# ETHERNET.net
KiCad netlist of a schematic drawn in Altium Designer
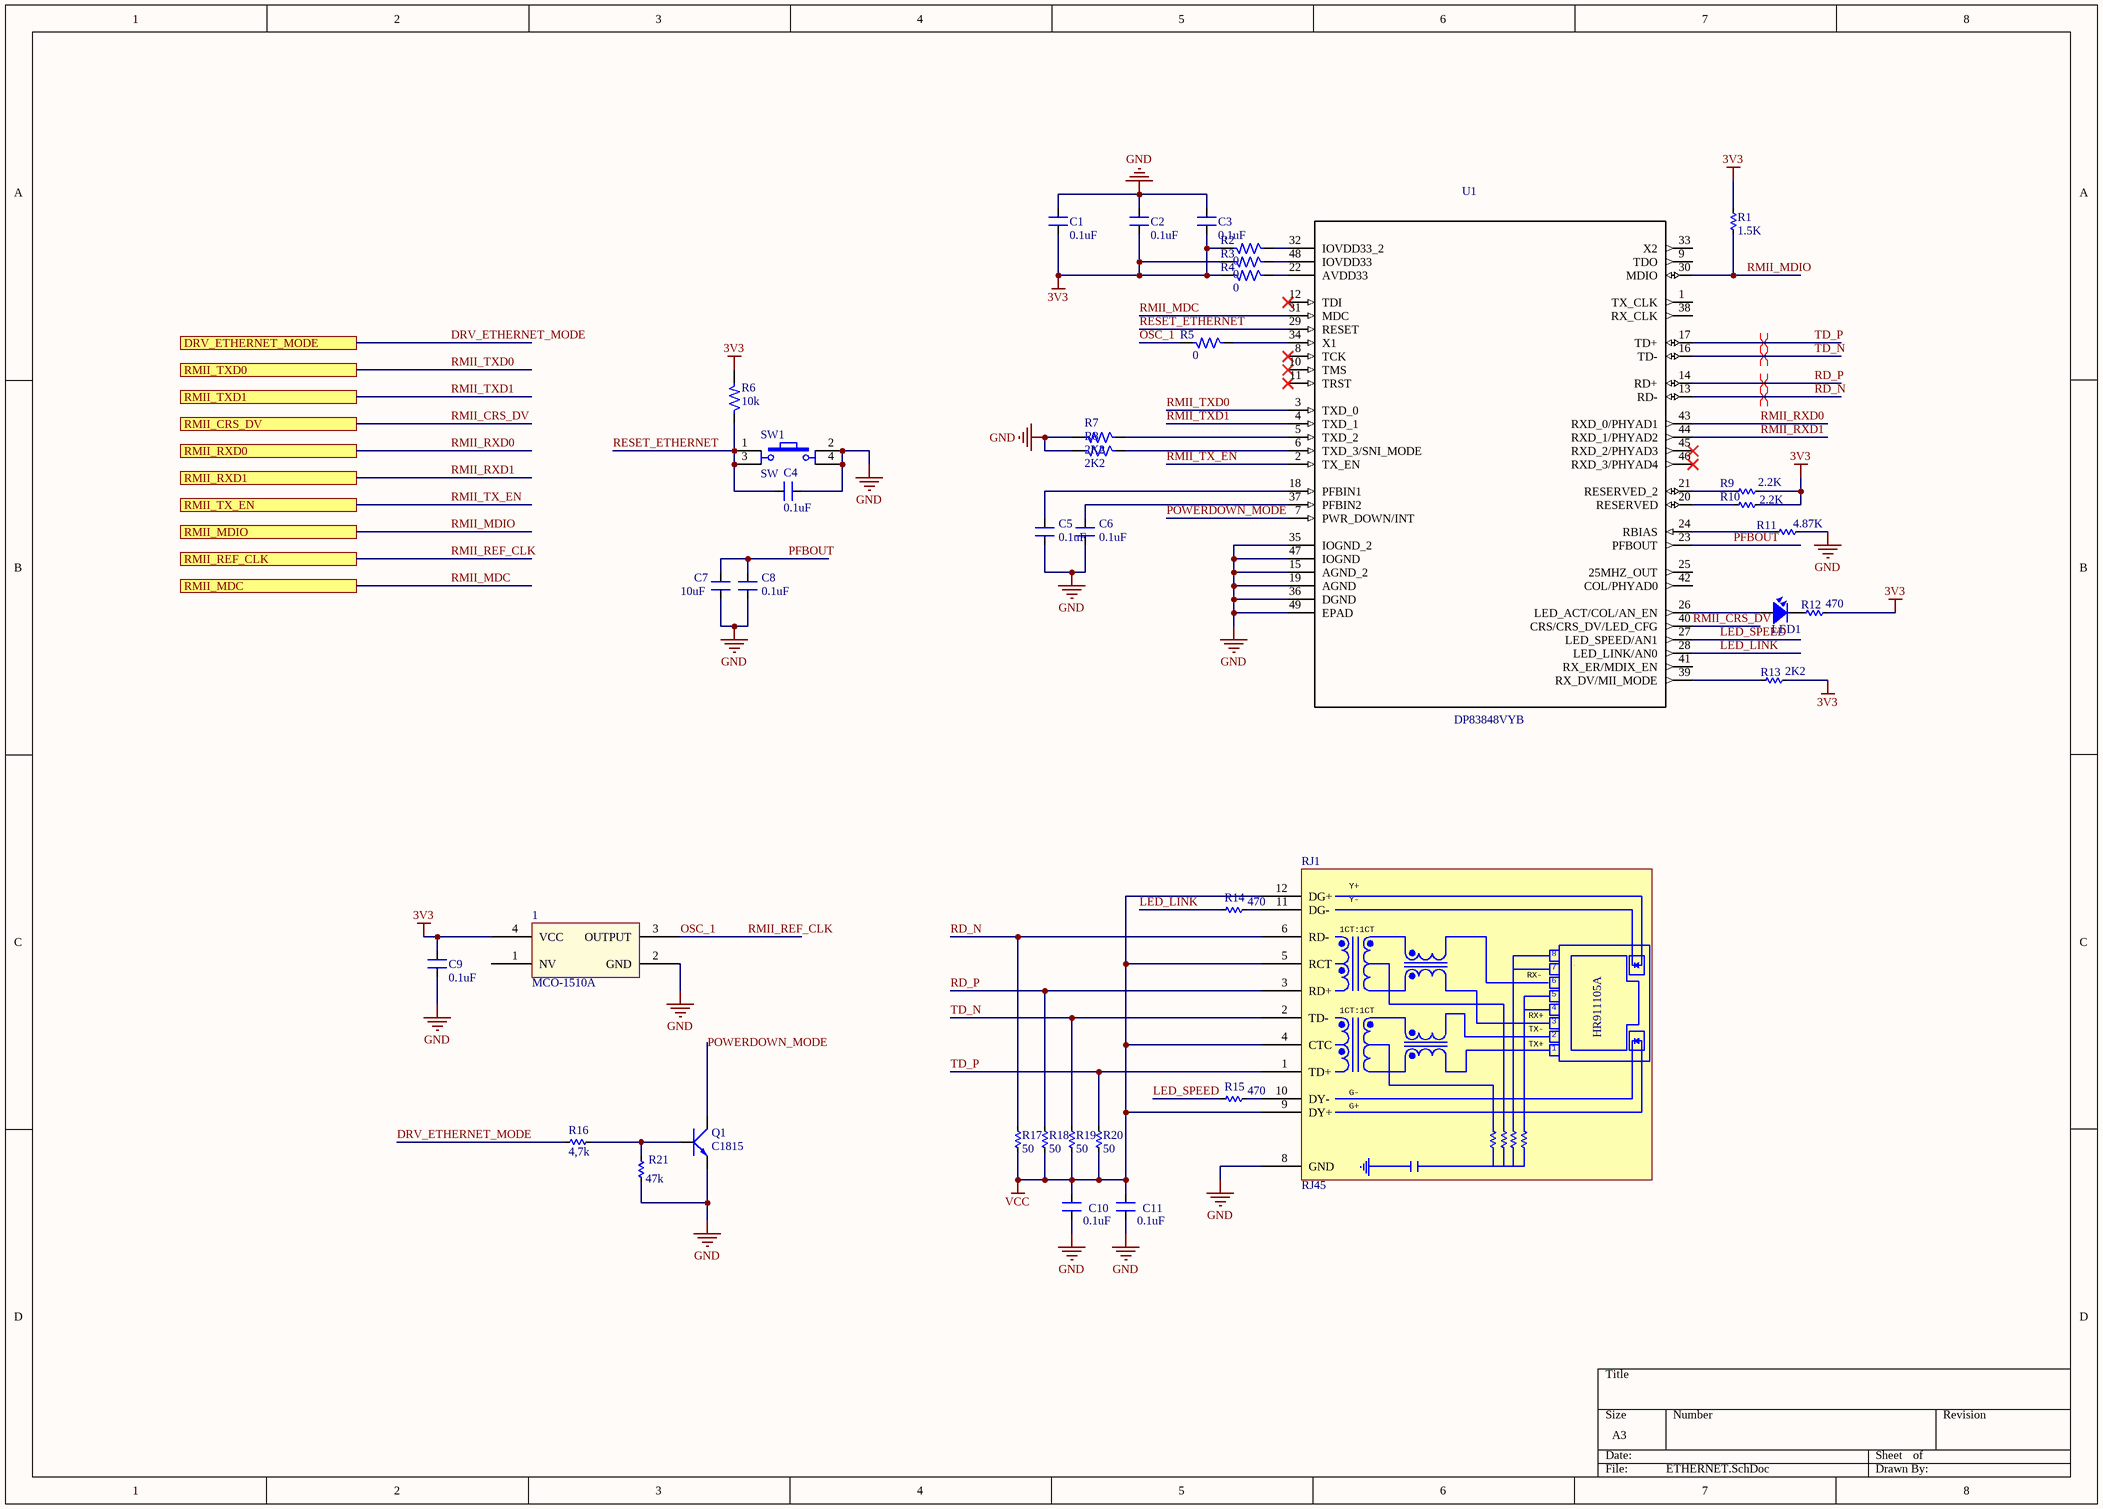
[diagram p0: ETHERNET.SchDoc]

(export (version "E")
  (design (tool "Eeschema 10.0.6"))
  (components
    (comp (ref "1") (value "MCO-1510A") (footprint "OSC_1510B") (libsource (lib "my_lib") (part "OSC50MhZ")))
    (comp (ref "C1")
      (value "0.1uF")
      (footprint "res 0805 - duplicate")
      (description "Cap SMD")
      (libsource (lib "PART") (part "CM"))
    )
    (comp (ref "C2")
      (value "0.1uF")
      (footprint "res 0805 - duplicate")
      (description "Cap SMD")
      (libsource (lib "PART") (part "CM"))
    )
    (comp (ref "C3")
      (value "0.1uF")
      (footprint "res 0805 - duplicate")
      (description "Cap SMD")
      (libsource (lib "PART") (part "CM"))
    )
    (comp (ref "C4")
      (value "0.1uF")
      (footprint "res 0805 - duplicate")
      (description "Cap SMD")
      (libsource (lib "PART") (part "CM"))
    )
    (comp (ref "C5")
      (value "0.1uF")
      (footprint "res 0805 - duplicate")
      (description "Cap SMD")
      (libsource (lib "PART") (part "CM"))
    )
    (comp (ref "C6")
      (value "0.1uF")
      (footprint "res 0805 - duplicate")
      (description "Cap SMD")
      (libsource (lib "PART") (part "CM"))
    )
    (comp (ref "C7")
      (value "10uF")
      (footprint "res 0805 - duplicate")
      (description "Cap SMD")
      (libsource (lib "PART") (part "CM"))
    )
    (comp (ref "C8")
      (value "0.1uF")
      (footprint "res 0805 - duplicate")
      (description "Cap SMD")
      (libsource (lib "PART") (part "CM"))
    )
    (comp (ref "C9")
      (value "0.1uF")
      (footprint "res 0805 - duplicate")
      (description "Cap SMD")
      (libsource (lib "PART") (part "CM"))
    )
    (comp (ref "C10")
      (value "0.1uF")
      (footprint "res 0805 - duplicate")
      (description "Cap SMD")
      (libsource (lib "PART") (part "CM"))
    )
    (comp (ref "C11")
      (value "0.1uF")
      (footprint "res 0805 - duplicate")
      (description "Cap SMD")
      (libsource (lib "PART") (part "CM"))
    )
    (comp (ref "LED1")
      (value "LED")
      (footprint "res 0805 - duplicate")
      (libsource (lib "LIBRARYabc") (part "LED SMD"))
    )
    (comp (ref "Q1")
      (value "C1815")
      (footprint "SOT23B")
      (description "NPN 600mW, ECB")
      (libsource (lib "syhaunguyen") (part "C1815"))
    )
    (comp (ref "R1")
      (value "1.5K")
      (footprint "res 0805 - duplicate")
      (description "Resistor")
      (fields
        (field (name "MANUFACTURER") "Generic Components")
        (field (name "PUBLISHER") "Altium Hobart Technology Centre")
      )
      (libsource (lib "LIBRARYabc") (part "Res-SMD"))
    )
    (comp (ref "R2")
      (value "0")
      (footprint "res 0805 - duplicate")
      (description "Resistor 1/4W")
      (libsource (lib "syhaunguyen") (part "R"))
    )
    (comp (ref "R3")
      (value "0")
      (footprint "res 0805 - duplicate")
      (description "Resistor 1/4W")
      (libsource (lib "syhaunguyen") (part "R"))
    )
    (comp (ref "R4")
      (value "0")
      (footprint "res 0805 - duplicate")
      (description "Resistor 1/4W")
      (libsource (lib "syhaunguyen") (part "R"))
    )
    (comp (ref "R5")
      (value "0")
      (footprint "res 0805 - duplicate")
      (description "Resistor 1/4W")
      (libsource (lib "syhaunguyen") (part "R"))
    )
    (comp (ref "R6")
      (value "10k")
      (footprint "res 0805 - duplicate")
      (description "Resistor 1/4W")
      (libsource (lib "syhaunguyen") (part "R"))
    )
    (comp (ref "R7")
      (value "2K2")
      (footprint "res 0805 - duplicate")
      (description "Resistor 1/4W")
      (libsource (lib "syhaunguyen") (part "R"))
    )
    (comp (ref "R8")
      (value "2K2")
      (footprint "res 0805 - duplicate")
      (description "Resistor 1/4W")
      (libsource (lib "syhaunguyen") (part "R"))
    )
    (comp (ref "R9")
      (value "2.2K")
      (footprint "res 0805 - duplicate")
      (description "Resistor")
      (fields
        (field (name "MANUFACTURER") "Generic Components")
        (field (name "PUBLISHER") "Altium Hobart Technology Centre")
      )
      (libsource (lib "LIBRARYabc") (part "Res-SMD"))
    )
    (comp (ref "R10")
      (value "2.2K")
      (footprint "res 0805 - duplicate")
      (description "Resistor")
      (fields
        (field (name "MANUFACTURER") "Generic Components")
        (field (name "PUBLISHER") "Altium Hobart Technology Centre")
      )
      (libsource (lib "LIBRARYabc") (part "Res-SMD"))
    )
    (comp (ref "R11")
      (value "4.87K")
      (footprint "res 0805 - duplicate")
      (description "Resistor")
      (fields
        (field (name "MANUFACTURER") "Generic Components")
        (field (name "PUBLISHER") "Altium Hobart Technology Centre")
      )
      (libsource (lib "LIBRARYabc") (part "Res-SMD"))
    )
    (comp (ref "R12")
      (value "470")
      (footprint "res 0805 - duplicate")
      (description "Resistor")
      (fields
        (field (name "MANUFACTURER") "Generic Components")
        (field (name "PUBLISHER") "Altium Hobart Technology Centre")
      )
      (libsource (lib "LIBRARYabc") (part "Res-SMD"))
    )
    (comp (ref "R13")
      (value "2K2")
      (footprint "res 0805 - duplicate")
      (description "Resistor")
      (fields
        (field (name "MANUFACTURER") "Generic Components")
        (field (name "PUBLISHER") "Altium Hobart Technology Centre")
      )
      (libsource (lib "LIBRARYabc") (part "Res-SMD"))
    )
    (comp (ref "R14")
      (value "470")
      (footprint "res 0805 - duplicate")
      (description "Resistor")
      (fields
        (field (name "MANUFACTURER") "Generic Components")
        (field (name "PUBLISHER") "Altium Hobart Technology Centre")
      )
      (libsource (lib "LIBRARYabc") (part "Res-SMD"))
    )
    (comp (ref "R15")
      (value "470")
      (footprint "res 0805 - duplicate")
      (description "Resistor")
      (fields
        (field (name "MANUFACTURER") "Generic Components")
        (field (name "PUBLISHER") "Altium Hobart Technology Centre")
      )
      (libsource (lib "LIBRARYabc") (part "Res-SMD"))
    )
    (comp (ref "R16")
      (value "4,7k")
      (footprint "res 0805 - duplicate")
      (description "Resistor")
      (fields
        (field (name "MANUFACTURER") "Generic Components")
        (field (name "PUBLISHER") "Altium Hobart Technology Centre")
      )
      (libsource (lib "LIBRARYabc") (part "Res-SMD"))
    )
    (comp (ref "R17")
      (value "50")
      (footprint "res 0805 - duplicate")
      (description "Resistor")
      (fields
        (field (name "MANUFACTURER") "Generic Components")
        (field (name "PUBLISHER") "Altium Hobart Technology Centre")
      )
      (libsource (lib "LIBRARYabc") (part "Res-SMD"))
    )
    (comp (ref "R18")
      (value "50")
      (footprint "res 0805 - duplicate")
      (description "Resistor")
      (fields
        (field (name "MANUFACTURER") "Generic Components")
        (field (name "PUBLISHER") "Altium Hobart Technology Centre")
      )
      (libsource (lib "LIBRARYabc") (part "Res-SMD"))
    )
    (comp (ref "R19")
      (value "50")
      (footprint "res 0805 - duplicate")
      (description "Resistor")
      (fields
        (field (name "MANUFACTURER") "Generic Components")
        (field (name "PUBLISHER") "Altium Hobart Technology Centre")
      )
      (libsource (lib "LIBRARYabc") (part "Res-SMD"))
    )
    (comp (ref "R20")
      (value "50")
      (footprint "res 0805 - duplicate")
      (description "Resistor")
      (fields
        (field (name "MANUFACTURER") "Generic Components")
        (field (name "PUBLISHER") "Altium Hobart Technology Centre")
      )
      (libsource (lib "LIBRARYabc") (part "Res-SMD"))
    )
    (comp (ref "R21")
      (value "47k")
      (footprint "res 0805 - duplicate")
      (description "Resistor")
      (fields
        (field (name "MANUFACTURER") "Generic Components")
        (field (name "PUBLISHER") "Altium Hobart Technology Centre")
      )
      (libsource (lib "LIBRARYabc") (part "Res-SMD"))
    )
    (comp (ref "RJ1")
      (value "RJ45")
      (footprint "RJ45 Tranfomer")
      (libsource (lib "syhaunguyen") (part "RJ45 - Tranfomer"))
    )
    (comp (ref "SW1")
      (value "SW")
      (footprint "button")
      (description "Switch button 4 pin")
      (libsource (lib "syhaunguyen") (part "SW4"))
    )
    (comp (ref "U1")
      (value "DP83848VYB")
      (footprint "QFP50P900X900X160-49N")
      (fields (field (name "MF") "Texas Instruments") (field (name "MP") "DP83848VYB/NOPB"))
      (libsource (lib "DP83848VYB") (part "DP83848VYB"))
    )
  )
  (nets
    (net (code "1") (name "/DRV_ETHERNET_MODE") (class "Default")
      (node (ref "R16") (pin "1") (pinfunction "1_1") (pintype "passive"))
    )
    (net (code "2") (name "/LED_LINK") (class "Default")
      (node (ref "R14") (pin "1") (pinfunction "1_1") (pintype "passive"))
      (node (ref "U1") (pin "28") (pinfunction "LED_LINK/AN0_28") (pintype "output"))
    )
    (net (code "3") (name "/LED_SPEED") (class "Default")
      (node (ref "R15") (pin "1") (pinfunction "1_1") (pintype "passive"))
      (node (ref "U1") (pin "27") (pinfunction "LED_SPEED/AN1_27") (pintype "output"))
    )
    (net (code "4") (name "/OSC_1") (class "Default")
      (node (ref "1") (pin "3") (pinfunction "OUTPUT_3") (pintype "passive"))
      (node (ref "R5") (pin "2") (pinfunction "2_2") (pintype "passive"))
    )
    (net (code "5") (name "/PFBOUT") (class "Default")
      (node (ref "C7") (pin "2") (pinfunction "2_2") (pintype "passive"))
      (node (ref "C8") (pin "2") (pinfunction "2_2") (pintype "passive"))
      (node (ref "U1") (pin "23") (pinfunction "PFBOUT_23") (pintype "output"))
    )
    (net (code "6") (name "/POWERDOWN_MODE") (class "Default")
      (node (ref "Q1") (pin "2") (pinfunction "C_2") (pintype "passive"))
      (node (ref "U1") (pin "7") (pinfunction "PWR_DOWN/INT_7") (pintype "input"))
    )
    (net (code "7") (name "/RD_N") (class "Default")
      (node (ref "R17") (pin "2") (pinfunction "2_2") (pintype "passive"))
      (node (ref "RJ1") (pin "6") (pinfunction "RD-_6") (pintype "passive"))
      (node (ref "U1") (pin "13") (pinfunction "RD-_13") (pintype "bidirectional"))
    )
    (net (code "8") (name "/RD_P") (class "Default")
      (node (ref "R18") (pin "2") (pinfunction "2_2") (pintype "passive"))
      (node (ref "RJ1") (pin "3") (pinfunction "RD+_3") (pintype "passive"))
      (node (ref "U1") (pin "14") (pinfunction "RD+_14") (pintype "bidirectional"))
    )
    (net (code "9") (name "/RESET_ETHERNET") (class "Default")
      (node (ref "C4") (pin "1") (pinfunction "1_1") (pintype "passive"))
      (node (ref "R6") (pin "1") (pinfunction "1_1") (pintype "passive"))
      (node (ref "SW1") (pin "1") (pintype "passive"))
      (node (ref "SW1") (pin "3") (pintype "passive"))
      (node (ref "U1") (pin "29") (pinfunction "RESET_29") (pintype "input"))
    )
    (net (code "10") (name "/RMII_CRS_DV") (class "Default")
      (node (ref "U1") (pin "40") (pinfunction "CRS/CRS_DV/LED_CFG_40") (pintype "output"))
    )
    (net (code "11") (name "/RMII_MDC") (class "Default")
      (node (ref "U1") (pin "31") (pinfunction "MDC_31") (pintype "input"))
    )
    (net (code "12") (name "/RMII_MDIO") (class "Default")
      (node (ref "R1") (pin "2") (pinfunction "2_2") (pintype "passive"))
      (node (ref "U1") (pin "30") (pinfunction "MDIO_30") (pintype "bidirectional"))
    )
    (net (code "13") (name "/RMII_RXD0") (class "Default")
      (node (ref "U1") (pin "43") (pinfunction "RXD_0/PHYAD1_43") (pintype "output"))
    )
    (net (code "14") (name "/RMII_RXD1") (class "Default")
      (node (ref "U1") (pin "44") (pinfunction "RXD_1/PHYAD2_44") (pintype "output"))
    )
    (net (code "15") (name "/RMII_TXD0") (class "Default")
      (node (ref "U1") (pin "3") (pinfunction "TXD_0_3") (pintype "input"))
    )
    (net (code "16") (name "/RMII_TXD1") (class "Default")
      (node (ref "U1") (pin "4") (pinfunction "TXD_1_4") (pintype "input"))
    )
    (net (code "17") (name "/RMII_TX_EN") (class "Default")
      (node (ref "U1") (pin "2") (pinfunction "TX_EN_2") (pintype "input"))
    )
    (net (code "18") (name "/TD_N") (class "Default")
      (node (ref "R19") (pin "2") (pinfunction "2_2") (pintype "passive"))
      (node (ref "RJ1") (pin "2") (pinfunction "TD-_2") (pintype "passive"))
      (node (ref "U1") (pin "16") (pinfunction "TD-_16") (pintype "bidirectional"))
    )
    (net (code "19") (name "/TD_P") (class "Default")
      (node (ref "R20") (pin "2") (pinfunction "2_2") (pintype "passive"))
      (node (ref "RJ1") (pin "1") (pinfunction "TD+_1") (pintype "passive"))
      (node (ref "U1") (pin "17") (pinfunction "TD+_17") (pintype "bidirectional"))
    )
    (net (code "20") (name "3V3") (class "Default")
      (node (ref "1") (pin "4") (pinfunction "VCC_4") (pintype "passive"))
      (node (ref "C1") (pin "2") (pinfunction "2_2") (pintype "passive"))
      (node (ref "C2") (pin "2") (pinfunction "2_2") (pintype "passive"))
      (node (ref "C3") (pin "2") (pinfunction "2_2") (pintype "passive"))
      (node (ref "C9") (pin "2") (pinfunction "2_2") (pintype "passive"))
      (node (ref "R1") (pin "1") (pinfunction "1_1") (pintype "passive"))
      (node (ref "R10") (pin "1") (pinfunction "1_1") (pintype "passive"))
      (node (ref "R12") (pin "1") (pinfunction "1_1") (pintype "passive"))
      (node (ref "R13") (pin "1") (pinfunction "1_1") (pintype "passive"))
      (node (ref "R2") (pin "2") (pinfunction "2_2") (pintype "passive"))
      (node (ref "R3") (pin "2") (pinfunction "2_2") (pintype "passive"))
      (node (ref "R4") (pin "2") (pinfunction "2_2") (pintype "passive"))
      (node (ref "R6") (pin "2") (pinfunction "2_2") (pintype "passive"))
      (node (ref "R9") (pin "1") (pinfunction "1_1") (pintype "passive"))
    )
    (net (code "21") (name "GND") (class "Default")
      (node (ref "1") (pin "2") (pinfunction "GND_2") (pintype "passive"))
      (node (ref "C1") (pin "1") (pinfunction "1_1") (pintype "passive"))
      (node (ref "C10") (pin "1") (pinfunction "1_1") (pintype "passive"))
      (node (ref "C11") (pin "1") (pinfunction "1_1") (pintype "passive"))
      (node (ref "C2") (pin "1") (pinfunction "1_1") (pintype "passive"))
      (node (ref "C3") (pin "1") (pinfunction "1_1") (pintype "passive"))
      (node (ref "C4") (pin "2") (pinfunction "2_2") (pintype "passive"))
      (node (ref "C5") (pin "1") (pinfunction "1_1") (pintype "passive"))
      (node (ref "C6") (pin "1") (pinfunction "1_1") (pintype "passive"))
      (node (ref "C7") (pin "1") (pinfunction "1_1") (pintype "passive"))
      (node (ref "C8") (pin "1") (pinfunction "1_1") (pintype "passive"))
      (node (ref "C9") (pin "1") (pinfunction "1_1") (pintype "passive"))
      (node (ref "Q1") (pin "1") (pinfunction "E_1") (pintype "passive"))
      (node (ref "R11") (pin "1") (pinfunction "1_1") (pintype "passive"))
      (node (ref "R21") (pin "1") (pinfunction "1_1") (pintype "passive"))
      (node (ref "R7") (pin "2") (pinfunction "2_2") (pintype "passive"))
      (node (ref "R8") (pin "2") (pinfunction "2_2") (pintype "passive"))
      (node (ref "RJ1") (pin "8") (pinfunction "GND_8") (pintype "power_in"))
      (node (ref "SW1") (pin "2") (pintype "passive"))
      (node (ref "SW1") (pin "4") (pintype "passive"))
      (node (ref "U1") (pin "15") (pinfunction "AGND_2_15") (pintype "passive"))
      (node (ref "U1") (pin "19") (pinfunction "AGND_19") (pintype "passive"))
      (node (ref "U1") (pin "35") (pinfunction "IOGND_2_35") (pintype "passive"))
      (node (ref "U1") (pin "36") (pinfunction "DGND_36") (pintype "passive"))
      (node (ref "U1") (pin "47") (pinfunction "IOGND_47") (pintype "passive"))
      (node (ref "U1") (pin "49") (pinfunction "EPAD_49") (pintype "passive"))
    )
    (net (code "22") (name "Net-(LED1-Pad2)") (class "Default")
      (node (ref "LED1") (pin "2") (pinfunction "2_2") (pintype "passive"))
      (node (ref "R12") (pin "2") (pinfunction "2_2") (pintype "passive"))
    )
    (net (code "23") (name "Net-(Q1-B)") (class "Default")
      (node (ref "Q1") (pin "3") (pinfunction "B_3") (pintype "passive"))
      (node (ref "R16") (pin "2") (pinfunction "2_2") (pintype "passive"))
      (node (ref "R21") (pin "2") (pinfunction "2_2") (pintype "passive"))
    )
    (net (code "24") (name "Net-(RJ1-DG-)") (class "Default")
      (node (ref "R14") (pin "2") (pinfunction "2_2") (pintype "passive"))
      (node (ref "RJ1") (pin "11") (pinfunction "DG-_11") (pintype "passive"))
    )
    (net (code "25") (name "Net-(RJ1-DY-)") (class "Default")
      (node (ref "R15") (pin "2") (pinfunction "2_2") (pintype "passive"))
      (node (ref "RJ1") (pin "10") (pinfunction "DY-_10") (pintype "passive"))
    )
    (net (code "26") (name "Net-(U1-AVDD33)") (class "Default")
      (node (ref "R4") (pin "1") (pinfunction "1_1") (pintype "passive"))
      (node (ref "U1") (pin "22") (pinfunction "AVDD33_22") (pintype "power_in"))
    )
    (net (code "27") (name "Net-(U1-IOVDD33)") (class "Default")
      (node (ref "R3") (pin "1") (pinfunction "1_1") (pintype "passive"))
      (node (ref "U1") (pin "48") (pinfunction "IOVDD33_48") (pintype "power_in"))
    )
    (net (code "28") (name "Net-(U1-IOVDD33_2)") (class "Default")
      (node (ref "R2") (pin "1") (pinfunction "1_1") (pintype "passive"))
      (node (ref "U1") (pin "32") (pinfunction "IOVDD33_2_32") (pintype "power_in"))
    )
    (net (code "29") (name "Net-(U1-LED_ACT{slash}COL{slash}AN_EN)") (class "Default")
      (node (ref "LED1") (pin "1") (pinfunction "1_1") (pintype "passive"))
      (node (ref "U1") (pin "26") (pinfunction "LED_ACT/COL/AN_EN_26") (pintype "output"))
    )
    (net (code "30") (name "Net-(U1-PFBIN1)") (class "Default")
      (node (ref "C5") (pin "2") (pinfunction "2_2") (pintype "passive"))
      (node (ref "U1") (pin "18") (pinfunction "PFBIN1_18") (pintype "input"))
    )
    (net (code "31") (name "Net-(U1-PFBIN2)") (class "Default")
      (node (ref "C6") (pin "2") (pinfunction "2_2") (pintype "passive"))
      (node (ref "U1") (pin "37") (pinfunction "PFBIN2_37") (pintype "input"))
    )
    (net (code "32") (name "Net-(U1-RBIAS)") (class "Default")
      (node (ref "R11") (pin "2") (pinfunction "2_2") (pintype "passive"))
      (node (ref "U1") (pin "24") (pinfunction "RBIAS_24") (pintype "input"))
    )
    (net (code "33") (name "Net-(U1-RESERVED)") (class "Default")
      (node (ref "R10") (pin "2") (pinfunction "2_2") (pintype "passive"))
      (node (ref "U1") (pin "20") (pinfunction "RESERVED_20") (pintype "bidirectional"))
    )
    (net (code "34") (name "Net-(U1-RESERVED_2)") (class "Default")
      (node (ref "R9") (pin "2") (pinfunction "2_2") (pintype "passive"))
      (node (ref "U1") (pin "21") (pinfunction "RESERVED_2_21") (pintype "bidirectional"))
    )
    (net (code "35") (name "Net-(U1-RX_DV{slash}MII_MODE)") (class "Default")
      (node (ref "R13") (pin "2") (pinfunction "2_2") (pintype "passive"))
      (node (ref "U1") (pin "39") (pinfunction "RX_DV/MII_MODE_39") (pintype "output"))
    )
    (net (code "36") (name "Net-(U1-TXD_2)") (class "Default")
      (node (ref "R7") (pin "1") (pinfunction "1_1") (pintype "passive"))
      (node (ref "U1") (pin "5") (pinfunction "TXD_2_5") (pintype "input"))
    )
    (net (code "37") (name "Net-(U1-TXD_3{slash}SNI_MODE)") (class "Default")
      (node (ref "R8") (pin "1") (pinfunction "1_1") (pintype "passive"))
      (node (ref "U1") (pin "6") (pinfunction "TXD_3/SNI_MODE_6") (pintype "input"))
    )
    (net (code "38") (name "Net-(U1-X1)") (class "Default")
      (node (ref "R5") (pin "1") (pinfunction "1_1") (pintype "passive"))
      (node (ref "U1") (pin "34") (pinfunction "X1_34") (pintype "input"))
    )
    (net (code "39") (name "VCC") (class "Default")
      (node (ref "C10") (pin "2") (pinfunction "2_2") (pintype "passive"))
      (node (ref "C11") (pin "2") (pinfunction "2_2") (pintype "passive"))
      (node (ref "R17") (pin "1") (pinfunction "1_1") (pintype "passive"))
      (node (ref "R18") (pin "1") (pinfunction "1_1") (pintype "passive"))
      (node (ref "R19") (pin "1") (pinfunction "1_1") (pintype "passive"))
      (node (ref "R20") (pin "1") (pinfunction "1_1") (pintype "passive"))
      (node (ref "RJ1") (pin "12") (pinfunction "DG+_12") (pintype "passive"))
      (node (ref "RJ1") (pin "4") (pinfunction "CTC_4") (pintype "passive"))
      (node (ref "RJ1") (pin "5") (pinfunction "RCT_5") (pintype "passive"))
      (node (ref "RJ1") (pin "9") (pinfunction "DY+_9") (pintype "passive"))
    )
    (net (code "40") (name "unconnected-(1-NV-Pad1)") (class "Default")
      (node (ref "1") (pin "1") (pinfunction "NV_1") (pintype "passive"))
    )
    (net (code "41") (name "unconnected-(U1-25MHZ_OUT-Pad25)") (class "Default")
      (node (ref "U1") (pin "25") (pinfunction "25MHZ_OUT_25") (pintype "output"))
    )
    (net (code "42") (name "unconnected-(U1-COL{slash}PHYAD0-Pad42)") (class "Default")
      (node (ref "U1") (pin "42") (pinfunction "COL/PHYAD0_42") (pintype "output"))
    )
    (net (code "43") (name "unconnected-(U1-RXD_2{slash}PHYAD3-Pad45)") (class "Default")
      (node (ref "U1") (pin "45") (pinfunction "RXD_2/PHYAD3_45") (pintype "output+no_connect"))
    )
    (net (code "44") (name "unconnected-(U1-RXD_3{slash}PHYAD4-Pad46)") (class "Default")
      (node (ref "U1") (pin "46") (pinfunction "RXD_3/PHYAD4_46") (pintype "output+no_connect"))
    )
    (net (code "45") (name "unconnected-(U1-RX_CLK-Pad38)") (class "Default")
      (node (ref "U1") (pin "38") (pinfunction "RX_CLK_38") (pintype "output"))
    )
    (net (code "46") (name "unconnected-(U1-RX_ER{slash}MDIX_EN-Pad41)") (class "Default")
      (node (ref "U1") (pin "41") (pinfunction "RX_ER/MDIX_EN_41") (pintype "output"))
    )
    (net (code "47") (name "unconnected-(U1-TCK-Pad8)") (class "Default")
      (node (ref "U1") (pin "8") (pinfunction "TCK_8") (pintype "input+no_connect"))
    )
    (net (code "48") (name "unconnected-(U1-TDI-Pad12)") (class "Default")
      (node (ref "U1") (pin "12") (pinfunction "TDI_12") (pintype "input+no_connect"))
    )
    (net (code "49") (name "unconnected-(U1-TDO-Pad9)") (class "Default")
      (node (ref "U1") (pin "9") (pinfunction "TDO_9") (pintype "output"))
    )
    (net (code "50") (name "unconnected-(U1-TMS-Pad10)") (class "Default")
      (node (ref "U1") (pin "10") (pinfunction "TMS_10") (pintype "input+no_connect"))
    )
    (net (code "51") (name "unconnected-(U1-TRST-Pad11)") (class "Default")
      (node (ref "U1") (pin "11") (pinfunction "TRST_11") (pintype "input+no_connect"))
    )
    (net (code "52") (name "unconnected-(U1-TX_CLK-Pad1)") (class "Default")
      (node (ref "U1") (pin "1") (pinfunction "TX_CLK_1") (pintype "output"))
    )
    (net (code "53") (name "unconnected-(U1-X2-Pad33)") (class "Default")
      (node (ref "U1") (pin "33") (pinfunction "X2_33") (pintype "output"))
    )
  )
)
